# relay_node.net
KiCad netlist of a schematic drawn in EAGLE
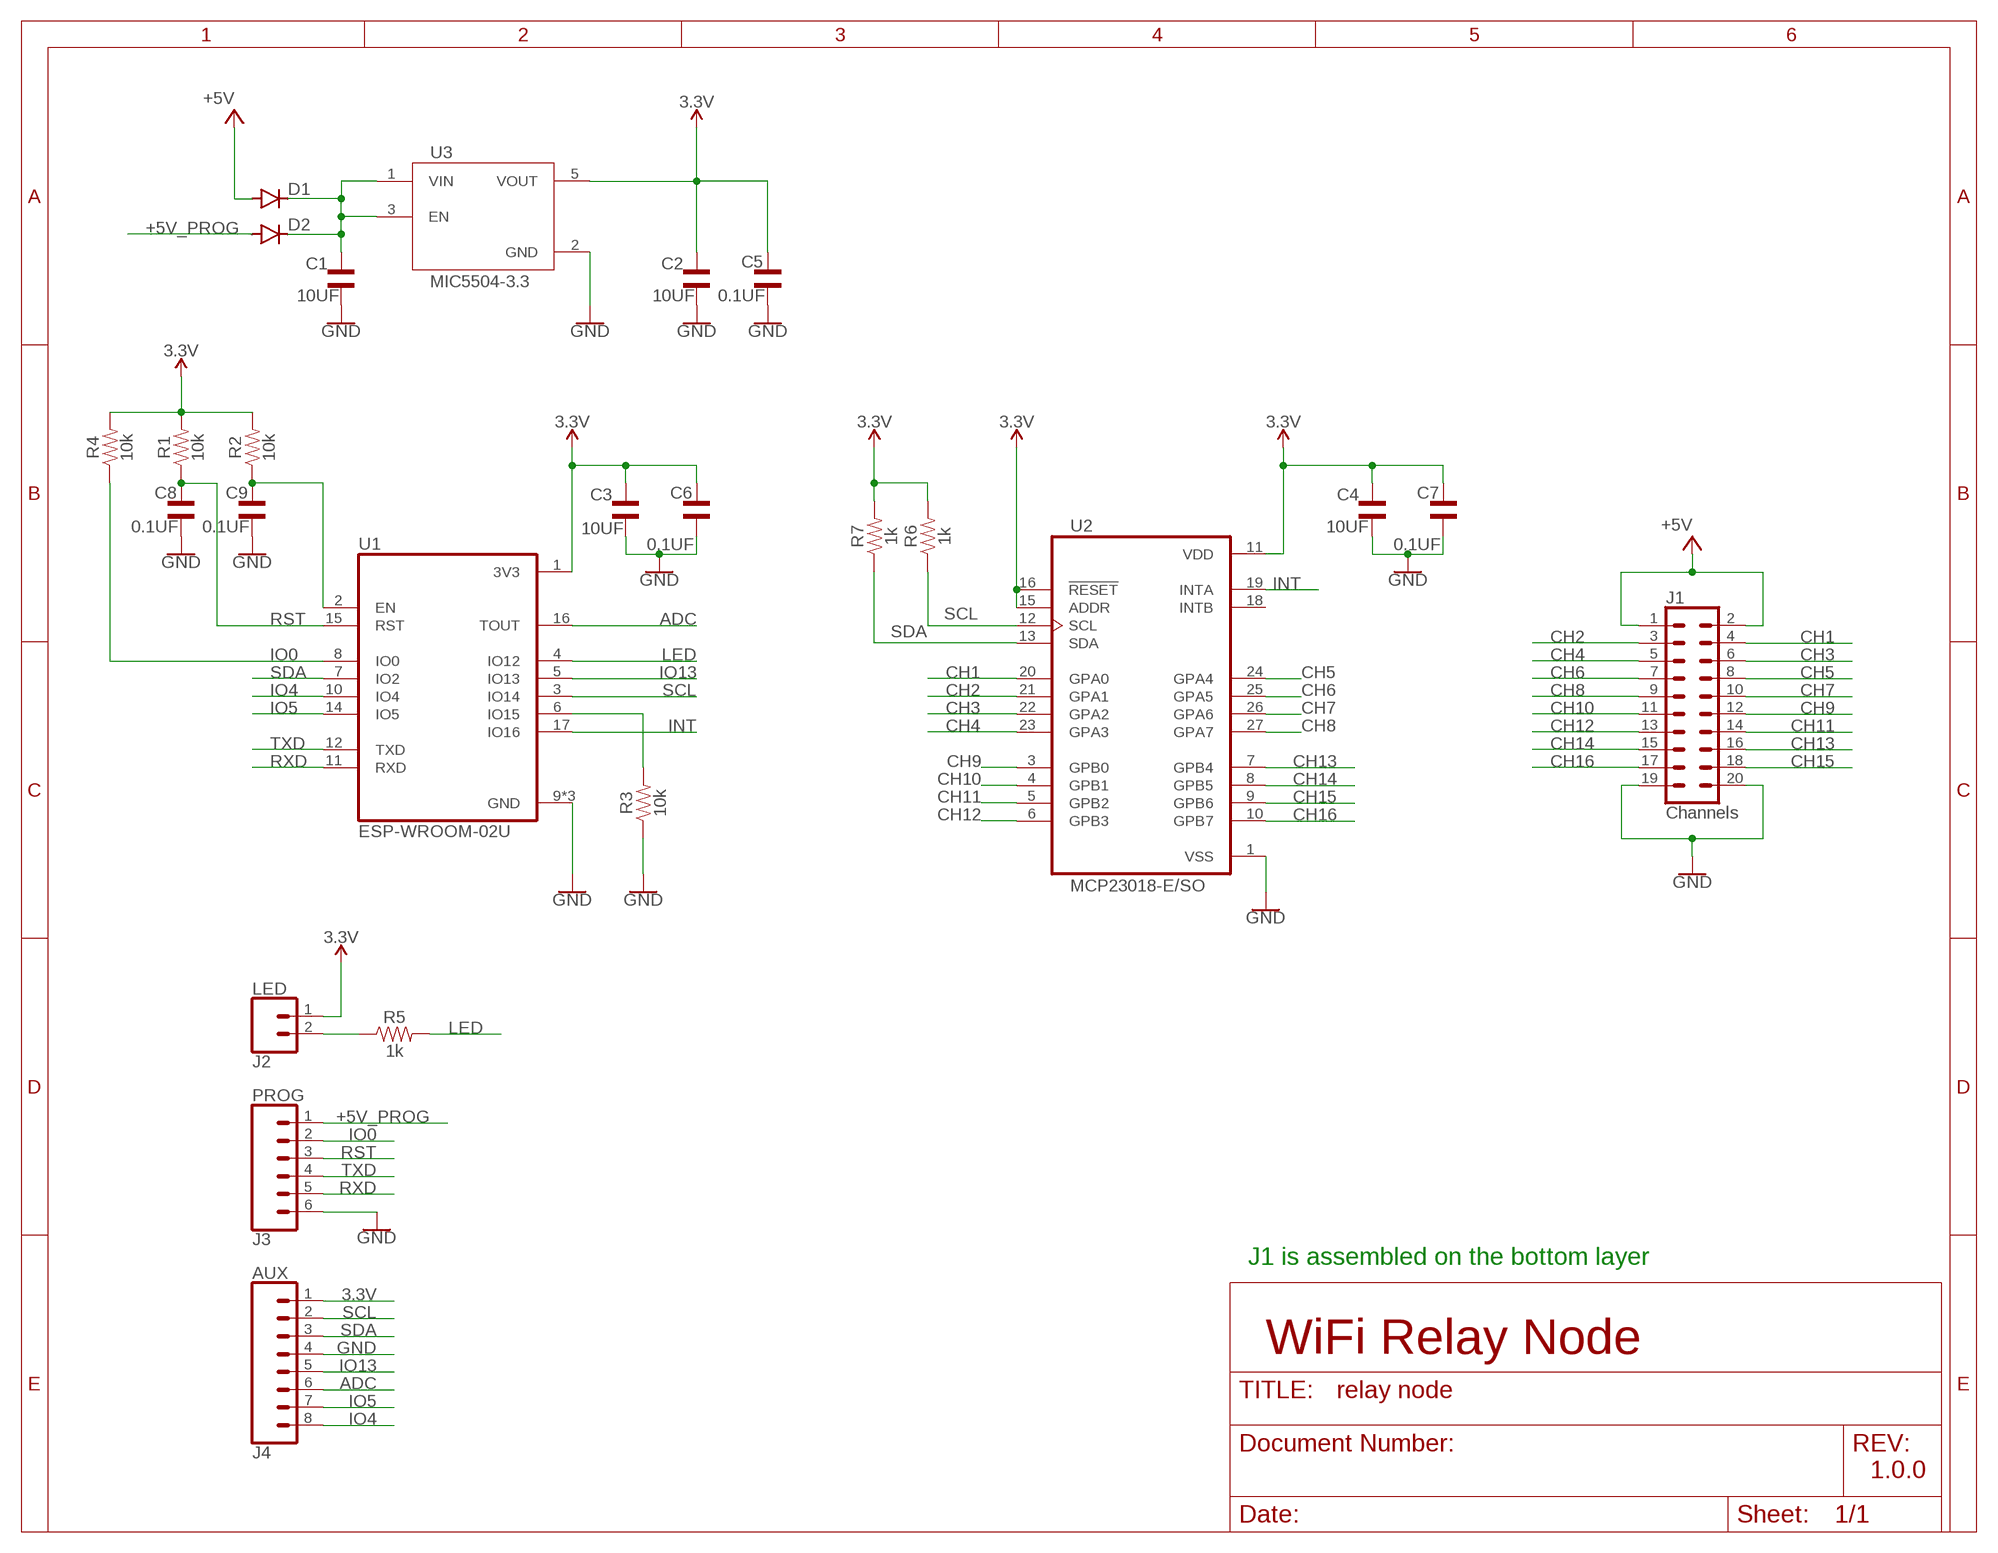
[diagram p0: schematic, sheet 1]

(export (version "E")
  (design (tool "Eeschema 10.0.6"))
  (components
    (comp (ref "C1")
      (value "10UF")
      (footprint "eagle-import:CAPC2012X135N")
      (fields
        (field (name "DIGI-KEY_PART_NUMBER") "490-10503-1-ND")
        (field (name "MF") "Murata")
        (field (name "MP") "GRM21BC81E106ME51L")
      )
      (libsource (lib "eagle-import") (part "10UF"))
    )
    (comp (ref "C2")
      (value "10UF")
      (footprint "eagle-import:CAPC2012X135N")
      (fields
        (field (name "DIGI-KEY_PART_NUMBER") "490-10503-1-ND")
        (field (name "MF") "Murata")
        (field (name "MP") "GRM21BC81E106ME51L")
      )
      (libsource (lib "eagle-import") (part "10UF"))
    )
    (comp (ref "C3")
      (value "10UF")
      (footprint "eagle-import:CAPC2012X135N")
      (fields
        (field (name "DIGI-KEY_PART_NUMBER") "490-10503-1-ND")
        (field (name "MF") "Murata")
        (field (name "MP") "GRM21BC81E106ME51L")
      )
      (libsource (lib "eagle-import") (part "10UF"))
    )
    (comp (ref "C4")
      (value "10UF")
      (footprint "eagle-import:CAPC2012X135N")
      (fields
        (field (name "DIGI-KEY_PART_NUMBER") "490-10503-1-ND")
        (field (name "MF") "Murata")
        (field (name "MP") "GRM21BC81E106ME51L")
      )
      (libsource (lib "eagle-import") (part "10UF"))
    )
    (comp (ref "C5")
      (value "0.1UF")
      (footprint "eagle-import:CAPC1608X90")
      (fields
        (field (name "DIGI-KEY_PART_NUMBER") "399-1100-1-ND")
        (field (name "MF") "KEMET")
        (field (name "MP") "C0603C104Z3VACTU")
      )
      (libsource (lib "eagle-import") (part "0.1UF"))
    )
    (comp (ref "C6")
      (value "0.1UF")
      (footprint "eagle-import:CAPC1608X90")
      (fields
        (field (name "DIGI-KEY_PART_NUMBER") "399-1100-1-ND")
        (field (name "MF") "KEMET")
        (field (name "MP") "C0603C104Z3VACTU")
      )
      (libsource (lib "eagle-import") (part "0.1UF"))
    )
    (comp (ref "C7")
      (value "0.1UF")
      (footprint "eagle-import:CAPC1608X90")
      (fields
        (field (name "DIGI-KEY_PART_NUMBER") "399-1100-1-ND")
        (field (name "MF") "KEMET")
        (field (name "MP") "C0603C104Z3VACTU")
      )
      (libsource (lib "eagle-import") (part "0.1UF"))
    )
    (comp (ref "C8")
      (value "0.1UF")
      (footprint "eagle-import:CAPC1608X90")
      (fields
        (field (name "DIGI-KEY_PART_NUMBER") "399-1100-1-ND")
        (field (name "MF") "KEMET")
        (field (name "MP") "C0603C104Z3VACTU")
      )
      (libsource (lib "eagle-import") (part "0.1UF"))
    )
    (comp (ref "C9")
      (value "0.1UF")
      (footprint "eagle-import:CAPC1608X90")
      (fields
        (field (name "DIGI-KEY_PART_NUMBER") "399-1100-1-ND")
        (field (name "MF") "KEMET")
        (field (name "MP") "C0603C104Z3VACTU")
      )
      (libsource (lib "eagle-import") (part "0.1UF"))
    )
    (comp (ref "D1")
      (value "MBR0520LT")
      (footprint "eagle-import:SOD123")
      (libsource (lib "eagle-import") (part "MBR0520LT"))
    )
    (comp (ref "D2")
      (value "MBR0520LT")
      (footprint "eagle-import:SOD123")
      (libsource (lib "eagle-import") (part "MBR0520LT"))
    )
    (comp (ref "J1")
      (value "Channels")
      (footprint "eagle-import:2X10_NOSILK")
      (libsource (lib "eagle-import") (part "CONN_10X2NOSILK"))
    )
    (comp (ref "J2")
      (value "LED")
      (footprint "eagle-import:1X02")
      (libsource (lib "eagle-import") (part "CONN_02"))
    )
    (comp (ref "J3")
      (value "PROG")
      (footprint "eagle-import:1X06")
      (libsource (lib "eagle-import") (part "CONN_06SILK_FEMALE_PTH"))
    )
    (comp (ref "J4")
      (value "AUX")
      (footprint "eagle-import:1X08")
      (libsource (lib "eagle-import") (part "CONN_08{dblquote}"))
    )
    (comp (ref "R1")
      (value "10k")
      (footprint "eagle-import:0603")
      (libsource (lib "eagle-import") (part "10KOHM-0603-1/10W-5%"))
    )
    (comp (ref "R2")
      (value "10k")
      (footprint "eagle-import:0603")
      (libsource (lib "eagle-import") (part "10KOHM-0603-1/10W-5%"))
    )
    (comp (ref "R3")
      (value "10k")
      (footprint "eagle-import:0603")
      (libsource (lib "eagle-import") (part "10KOHM-0603-1/10W-5%"))
    )
    (comp (ref "R4")
      (value "10k")
      (footprint "eagle-import:0603")
      (libsource (lib "eagle-import") (part "10KOHM-0603-1/10W-5%"))
    )
    (comp (ref "R5")
      (value "1k")
      (footprint "eagle-import:0603")
      (libsource (lib "eagle-import") (part "1KOHM-0603-1/10W-5%"))
    )
    (comp (ref "R6")
      (value "1k")
      (footprint "eagle-import:0603")
      (libsource (lib "eagle-import") (part "1KOHM-0603-1/10W-5%"))
    )
    (comp (ref "R7")
      (value "1k")
      (footprint "eagle-import:0603")
      (libsource (lib "eagle-import") (part "1KOHM-0603-1/10W-5%"))
    )
    (comp (ref "U1")
      (value "ESP-WROOM-02U")
      (footprint "eagle-import:MODULE_ESP-WROOM-02U")
      (fields (field (name "MF") "Espressif Systems"))
      (libsource (lib "eagle-import") (part "ESP-WROOM-02U"))
    )
    (comp (ref "U2")
      (value "MCP23018-E/SO")
      (footprint "eagle-import:SOIC127P1030X265-28N")
      (fields (field (name "MF") "Microchip"))
      (libsource (lib "eagle-import") (part "MCP23018-E/SO"))
    )
    (comp (ref "U3")
      (value "MIC5504-3.3")
      (footprint "eagle-import:SOT95P280X145-5N")
      (fields
        (field (name "DIGI-KEY_PART_NUMBER") "MIC5504-3.3YM5-T5CT-ND")
        (field (name "MF") "Microchip")
        (field (name "MP") "MIC5504-3.3YM5-T5")
      )
      (libsource (lib "eagle-import") (part "MIC5504-3.3YM5-T5"))
    )
  )
  (nets
    (net (code "1") (name "+5V") (class "Default")
      (node (ref "D1") (pin "A") (pinfunction "A_A") (pintype "passive"))
      (node (ref "J1") (pin "1") (pinfunction "1_1") (pintype "passive"))
      (node (ref "J1") (pin "2") (pinfunction "2_2") (pintype "passive"))
    )
    (net (code "2") (name "/+5V_PROG") (class "Default")
      (node (ref "D2") (pin "A") (pinfunction "A_A") (pintype "passive"))
      (node (ref "J3") (pin "1") (pinfunction "1_1") (pintype "passive"))
    )
    (net (code "3") (name "/ADC") (class "Default")
      (node (ref "J4") (pin "6") (pinfunction "6_6") (pintype "passive"))
      (node (ref "U1") (pin "16") (pinfunction "TOUT_16") (pintype "bidirectional"))
    )
    (net (code "4") (name "/CH1") (class "Default")
      (node (ref "J1") (pin "4") (pinfunction "4_4") (pintype "passive"))
      (node (ref "U2") (pin "20") (pinfunction "GPA0_20") (pintype "bidirectional"))
    )
    (net (code "5") (name "/CH2") (class "Default")
      (node (ref "J1") (pin "3") (pinfunction "3_3") (pintype "passive"))
      (node (ref "U2") (pin "21") (pinfunction "GPA1_21") (pintype "bidirectional"))
    )
    (net (code "6") (name "/CH3") (class "Default")
      (node (ref "J1") (pin "6") (pinfunction "6_6") (pintype "passive"))
      (node (ref "U2") (pin "22") (pinfunction "GPA2_22") (pintype "bidirectional"))
    )
    (net (code "7") (name "/CH4") (class "Default")
      (node (ref "J1") (pin "5") (pinfunction "5_5") (pintype "passive"))
      (node (ref "U2") (pin "23") (pinfunction "GPA3_23") (pintype "bidirectional"))
    )
    (net (code "8") (name "/CH5") (class "Default")
      (node (ref "J1") (pin "8") (pinfunction "8_8") (pintype "passive"))
      (node (ref "U2") (pin "24") (pinfunction "GPA4_24") (pintype "bidirectional"))
    )
    (net (code "9") (name "/CH6") (class "Default")
      (node (ref "J1") (pin "7") (pinfunction "7_7") (pintype "passive"))
      (node (ref "U2") (pin "25") (pinfunction "GPA5_25") (pintype "bidirectional"))
    )
    (net (code "10") (name "/CH7") (class "Default")
      (node (ref "J1") (pin "10") (pinfunction "10_10") (pintype "passive"))
      (node (ref "U2") (pin "26") (pinfunction "GPA6_26") (pintype "bidirectional"))
    )
    (net (code "11") (name "/CH8") (class "Default")
      (node (ref "J1") (pin "9") (pinfunction "9_9") (pintype "passive"))
      (node (ref "U2") (pin "27") (pinfunction "GPA7_27") (pintype "bidirectional"))
    )
    (net (code "12") (name "/CH9") (class "Default")
      (node (ref "J1") (pin "12") (pinfunction "12_12") (pintype "passive"))
      (node (ref "U2") (pin "3") (pinfunction "GPB0_3") (pintype "bidirectional"))
    )
    (net (code "13") (name "/CH10") (class "Default")
      (node (ref "J1") (pin "11") (pinfunction "11_11") (pintype "passive"))
      (node (ref "U2") (pin "4") (pinfunction "GPB1_4") (pintype "bidirectional"))
    )
    (net (code "14") (name "/CH11") (class "Default")
      (node (ref "J1") (pin "14") (pinfunction "14_14") (pintype "passive"))
      (node (ref "U2") (pin "5") (pinfunction "GPB2_5") (pintype "bidirectional"))
    )
    (net (code "15") (name "/CH12") (class "Default")
      (node (ref "J1") (pin "13") (pinfunction "13_13") (pintype "passive"))
      (node (ref "U2") (pin "6") (pinfunction "GPB3_6") (pintype "bidirectional"))
    )
    (net (code "16") (name "/CH13") (class "Default")
      (node (ref "J1") (pin "16") (pinfunction "16_16") (pintype "passive"))
      (node (ref "U2") (pin "7") (pinfunction "GPB4_7") (pintype "bidirectional"))
    )
    (net (code "17") (name "/CH14") (class "Default")
      (node (ref "J1") (pin "15") (pinfunction "15_15") (pintype "passive"))
      (node (ref "U2") (pin "8") (pinfunction "GPB5_8") (pintype "bidirectional"))
    )
    (net (code "18") (name "/CH15") (class "Default")
      (node (ref "J1") (pin "18") (pinfunction "18_18") (pintype "passive"))
      (node (ref "U2") (pin "9") (pinfunction "GPB6_9") (pintype "bidirectional"))
    )
    (net (code "19") (name "/CH16") (class "Default")
      (node (ref "J1") (pin "17") (pinfunction "17_17") (pintype "passive"))
      (node (ref "U2") (pin "10") (pinfunction "GPB7_10") (pintype "bidirectional"))
    )
    (net (code "20") (name "/INT") (class "Default")
      (node (ref "U1") (pin "17") (pinfunction "IO16_17") (pintype "bidirectional"))
      (node (ref "U2") (pin "19") (pinfunction "INTA_19") (pintype "output"))
    )
    (net (code "21") (name "/IO0") (class "Default")
      (node (ref "J3") (pin "2") (pinfunction "2_2") (pintype "passive"))
      (node (ref "R4") (pin "1") (pinfunction "1_1") (pintype "passive"))
      (node (ref "U1") (pin "8") (pinfunction "IO0_8") (pintype "bidirectional"))
    )
    (net (code "22") (name "/IO4") (class "Default")
      (node (ref "J4") (pin "8") (pinfunction "8_8") (pintype "passive"))
      (node (ref "U1") (pin "10") (pinfunction "IO4_10") (pintype "bidirectional"))
    )
    (net (code "23") (name "/IO5") (class "Default")
      (node (ref "J4") (pin "7") (pinfunction "7_7") (pintype "passive"))
      (node (ref "U1") (pin "14") (pinfunction "IO5_14") (pintype "bidirectional"))
    )
    (net (code "24") (name "/IO13") (class "Default")
      (node (ref "J4") (pin "5") (pinfunction "5_5") (pintype "passive"))
      (node (ref "U1") (pin "5") (pinfunction "IO13_5") (pintype "bidirectional"))
    )
    (net (code "25") (name "/LED") (class "Default")
      (node (ref "R5") (pin "2") (pinfunction "2_2") (pintype "passive"))
      (node (ref "U1") (pin "4") (pinfunction "IO12_4") (pintype "bidirectional"))
    )
    (net (code "26") (name "/RST") (class "Default")
      (node (ref "C8") (pin "1") (pinfunction "1_1") (pintype "passive"))
      (node (ref "J3") (pin "3") (pinfunction "3_3") (pintype "passive"))
      (node (ref "R1") (pin "1") (pinfunction "1_1") (pintype "passive"))
      (node (ref "U1") (pin "15") (pinfunction "RST_15") (pintype "input"))
    )
    (net (code "27") (name "/RXD") (class "Default")
      (node (ref "J3") (pin "5") (pinfunction "5_5") (pintype "passive"))
      (node (ref "U1") (pin "11") (pinfunction "RXD_11") (pintype "bidirectional"))
    )
    (net (code "28") (name "/SCL") (class "Default")
      (node (ref "J4") (pin "2") (pinfunction "2_2") (pintype "passive"))
      (node (ref "R6") (pin "1") (pinfunction "1_1") (pintype "passive"))
      (node (ref "U1") (pin "3") (pinfunction "IO14_3") (pintype "bidirectional"))
      (node (ref "U2") (pin "12") (pinfunction "SCL_12") (pintype "input"))
    )
    (net (code "29") (name "/SDA") (class "Default")
      (node (ref "J4") (pin "3") (pinfunction "3_3") (pintype "passive"))
      (node (ref "R7") (pin "1") (pinfunction "1_1") (pintype "passive"))
      (node (ref "U1") (pin "7") (pinfunction "IO2_7") (pintype "bidirectional"))
      (node (ref "U2") (pin "13") (pinfunction "SDA_13") (pintype "bidirectional"))
    )
    (net (code "30") (name "/TXD") (class "Default")
      (node (ref "J3") (pin "4") (pinfunction "4_4") (pintype "passive"))
      (node (ref "U1") (pin "12") (pinfunction "TXD_12") (pintype "bidirectional"))
    )
    (net (code "31") (name "3.3V") (class "Default")
      (node (ref "C2") (pin "1") (pinfunction "1_1") (pintype "passive"))
      (node (ref "C3") (pin "1") (pinfunction "1_1") (pintype "passive"))
      (node (ref "C4") (pin "1") (pinfunction "1_1") (pintype "passive"))
      (node (ref "C5") (pin "1") (pinfunction "1_1") (pintype "passive"))
      (node (ref "C6") (pin "1") (pinfunction "1_1") (pintype "passive"))
      (node (ref "C7") (pin "1") (pinfunction "1_1") (pintype "passive"))
      (node (ref "J2") (pin "1") (pinfunction "1_1") (pintype "passive"))
      (node (ref "J4") (pin "1") (pinfunction "1_1") (pintype "passive"))
      (node (ref "R1") (pin "2") (pinfunction "2_2") (pintype "passive"))
      (node (ref "R2") (pin "2") (pinfunction "2_2") (pintype "passive"))
      (node (ref "R4") (pin "2") (pinfunction "2_2") (pintype "passive"))
      (node (ref "R6") (pin "2") (pinfunction "2_2") (pintype "passive"))
      (node (ref "R7") (pin "2") (pinfunction "2_2") (pintype "passive"))
      (node (ref "U1") (pin "1") (pinfunction "3V3_1") (pintype "power_in"))
      (node (ref "U2") (pin "11") (pinfunction "VDD_11") (pintype "power_in"))
      (node (ref "U2") (pin "15") (pinfunction "ADDR_15") (pintype "input"))
      (node (ref "U2") (pin "16") (pinfunction "~{RESET}_16") (pintype "input"))
      (node (ref "U3") (pin "5") (pinfunction "VOUT_5") (pintype "power_in"))
    )
    (net (code "32") (name "GND") (class "Default")
      (node (ref "C1") (pin "2") (pinfunction "2_2") (pintype "passive"))
      (node (ref "C2") (pin "2") (pinfunction "2_2") (pintype "passive"))
      (node (ref "C3") (pin "2") (pinfunction "2_2") (pintype "passive"))
      (node (ref "C4") (pin "2") (pinfunction "2_2") (pintype "passive"))
      (node (ref "C5") (pin "2") (pinfunction "2_2") (pintype "passive"))
      (node (ref "C6") (pin "2") (pinfunction "2_2") (pintype "passive"))
      (node (ref "C7") (pin "2") (pinfunction "2_2") (pintype "passive"))
      (node (ref "C8") (pin "2") (pinfunction "2_2") (pintype "passive"))
      (node (ref "C9") (pin "2") (pinfunction "2_2") (pintype "passive"))
      (node (ref "J1") (pin "19") (pinfunction "19_19") (pintype "passive"))
      (node (ref "J1") (pin "20") (pinfunction "20_20") (pintype "passive"))
      (node (ref "J3") (pin "6") (pinfunction "6_6") (pintype "passive"))
      (node (ref "J4") (pin "4") (pinfunction "4_4") (pintype "passive"))
      (node (ref "R3") (pin "1") (pinfunction "1_1") (pintype "passive"))
      (node (ref "U1") (pin "13") (pinfunction "GND_13") (pintype "power_in"))
      (node (ref "U1") (pin "18") (pinfunction "GND_18") (pintype "power_in"))
      (node (ref "U1") (pin "9") (pinfunction "GND_9") (pintype "power_in"))
      (node (ref "U2") (pin "1") (pinfunction "VSS_1") (pintype "power_in"))
      (node (ref "U3") (pin "2") (pinfunction "GND_2") (pintype "power_in"))
    )
    (net (code "33") (name "Net-(J2-Pad2)") (class "Default")
      (node (ref "J2") (pin "2") (pinfunction "2_2") (pintype "passive"))
      (node (ref "R5") (pin "1") (pinfunction "1_1") (pintype "passive"))
    )
    (net (code "34") (name "Net-(U1-EN)") (class "Default")
      (node (ref "C9") (pin "1") (pinfunction "1_1") (pintype "passive"))
      (node (ref "R2") (pin "1") (pinfunction "1_1") (pintype "passive"))
      (node (ref "U1") (pin "2") (pinfunction "EN_2") (pintype "input"))
    )
    (net (code "35") (name "Net-(U1-IO15)") (class "Default")
      (node (ref "R3") (pin "2") (pinfunction "2_2") (pintype "passive"))
      (node (ref "U1") (pin "6") (pinfunction "IO15_6") (pintype "bidirectional"))
    )
    (net (code "36") (name "Net-(U3-EN)") (class "Default")
      (node (ref "C1") (pin "1") (pinfunction "1_1") (pintype "passive"))
      (node (ref "D1") (pin "C") (pinfunction "C_C") (pintype "passive"))
      (node (ref "D2") (pin "C") (pinfunction "C_C") (pintype "passive"))
      (node (ref "U3") (pin "1") (pinfunction "VIN_1") (pintype "power_in"))
      (node (ref "U3") (pin "3") (pinfunction "EN_3") (pintype "input"))
    )
    (net (code "37") (name "unconnected-(U2-INTB-Pad18)") (class "Default")
      (node (ref "U2") (pin "18") (pinfunction "INTB_18") (pintype "output"))
    )
  )
)
